# Sheet1.net
KiCad netlist of a schematic drawn in Altium Designer
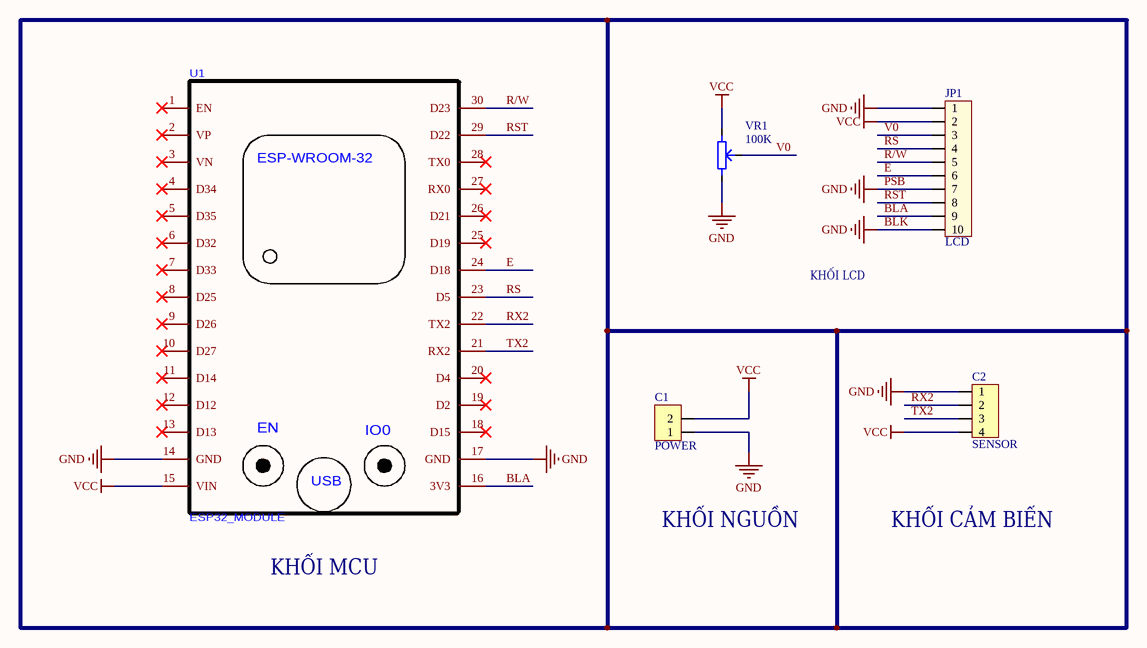
[diagram p0: Sheet1.SchDoc]

(export (version "E")
  (design (tool "Eeschema 10.0.6"))
  (components
    (comp (ref "C1")
      (value "POWER")
      (footprint "Header2")
      (description "Header IDC, 2 x 1 Pin Vertical 2.54mm Pitch (Non-Boxed, Male)")
      (fields
        (field (name "MANUFACTURER") "Würth Elektronik eiSos GmbH")
        (field (name "PARTNO") "613002143121")
        (field (name "CREATED BY") "Karrer Zheng")
      )
      (libsource (lib "myLib_v1") (part "Header2"))
    )
    (comp (ref "C2")
      (value "SENSOR")
      (footprint "Header4")
      (description "Header IDC, 4 x 1 Pin Vertical 2.54mm Pitch (Non-Boxed, Male)")
      (fields
        (field (name "MANUFACTURER") "Würth Elektronik eiSos GmbH")
        (field (name "PARTNO") "613002143121")
        (field (name "CREATED BY") "Karrer Zheng")
      )
      (libsource (lib "myLib_v1") (part "Header4"))
    )
    (comp (ref "JP1")
      (value "LCD")
      (footprint "Header10")
      (description "Connector 10")
      (libsource (lib "myLib_v1") (part "Header10"))
    )
    (comp (ref "U1")
      (value "ESP32_MODULE")
      (footprint "ESP32-WIFIMODULE-FOOTPRINT")
      (libsource (lib "myLib_v1") (part "ESP32_MODULE copy"))
    )
    (comp (ref "VR1")
      (value "100K")
      (footprint "Bien Tro Tam Giac Dung")
      (description "Cắm")
      (libsource (lib "Altium_Lib_by_KhueNguyenCreator") (part "Bien tro tam giac 100K Dung"))
    )
  )
  (nets
    (net (code "1") (name "/BLA") (class "Default")
      (node (ref "JP1") (pin "9") (pinfunction "9_9") (pintype "passive"))
      (node (ref "U1") (pin "16") (pinfunction "3V3_16") (pintype "passive"))
    )
    (net (code "2") (name "/E") (class "Default")
      (node (ref "JP1") (pin "6") (pinfunction "6_6") (pintype "passive"))
      (node (ref "U1") (pin "24") (pinfunction "D18_24") (pintype "passive"))
    )
    (net (code "3") (name "/RS") (class "Default")
      (node (ref "JP1") (pin "4") (pinfunction "4_4") (pintype "passive"))
      (node (ref "U1") (pin "23") (pinfunction "D5_23") (pintype "passive"))
    )
    (net (code "4") (name "/RST") (class "Default")
      (node (ref "JP1") (pin "8") (pinfunction "8_8") (pintype "passive"))
      (node (ref "U1") (pin "29") (pinfunction "D22_29") (pintype "passive"))
    )
    (net (code "5") (name "/RX2") (class "Default")
      (node (ref "C2") (pin "2") (pinfunction "2_2") (pintype "passive"))
      (node (ref "U1") (pin "22") (pinfunction "TX2_22") (pintype "passive"))
    )
    (net (code "6") (name "/R{slash}W") (class "Default")
      (node (ref "JP1") (pin "5") (pinfunction "5_5") (pintype "passive"))
      (node (ref "U1") (pin "30") (pinfunction "D23_30") (pintype "passive"))
    )
    (net (code "7") (name "/TX2") (class "Default")
      (node (ref "C2") (pin "3") (pinfunction "3_3") (pintype "passive"))
      (node (ref "U1") (pin "21") (pinfunction "RX2_21") (pintype "passive"))
    )
    (net (code "8") (name "/V0") (class "Default")
      (node (ref "JP1") (pin "3") (pinfunction "3_3") (pintype "passive"))
      (node (ref "VR1") (pin "2") (pinfunction "2_2") (pintype "passive"))
    )
    (net (code "9") (name "GND") (class "Default")
      (node (ref "C1") (pin "1") (pinfunction "1_1") (pintype "passive"))
      (node (ref "C2") (pin "1") (pinfunction "1_1") (pintype "passive"))
      (node (ref "JP1") (pin "1") (pinfunction "1_1") (pintype "passive"))
      (node (ref "JP1") (pin "10") (pinfunction "10_10") (pintype "passive"))
      (node (ref "JP1") (pin "7") (pinfunction "7_7") (pintype "passive"))
      (node (ref "U1") (pin "14") (pinfunction "GND_14") (pintype "passive"))
      (node (ref "U1") (pin "17") (pinfunction "GND_17") (pintype "passive"))
      (node (ref "VR1") (pin "3") (pinfunction "3_3") (pintype "passive"))
    )
    (net (code "10") (name "VCC") (class "Default")
      (node (ref "C1") (pin "2") (pinfunction "2_2") (pintype "passive"))
      (node (ref "C2") (pin "4") (pinfunction "4_4") (pintype "passive"))
      (node (ref "JP1") (pin "2") (pinfunction "2_2") (pintype "passive"))
      (node (ref "U1") (pin "15") (pinfunction "VIN_15") (pintype "passive"))
      (node (ref "VR1") (pin "1") (pinfunction "1_1") (pintype "passive"))
    )
    (net (code "11") (name "unconnected-(U1-D2-Pad19)") (class "Default")
      (node (ref "U1") (pin "19") (pinfunction "D2_19") (pintype "passive+no_connect"))
    )
    (net (code "12") (name "unconnected-(U1-D4-Pad20)") (class "Default")
      (node (ref "U1") (pin "20") (pinfunction "D4_20") (pintype "passive+no_connect"))
    )
    (net (code "13") (name "unconnected-(U1-D12-Pad12)") (class "Default")
      (node (ref "U1") (pin "12") (pinfunction "D12_12") (pintype "passive+no_connect"))
    )
    (net (code "14") (name "unconnected-(U1-D13-Pad13)") (class "Default")
      (node (ref "U1") (pin "13") (pinfunction "D13_13") (pintype "passive+no_connect"))
    )
    (net (code "15") (name "unconnected-(U1-D14-Pad11)") (class "Default")
      (node (ref "U1") (pin "11") (pinfunction "D14_11") (pintype "passive+no_connect"))
    )
    (net (code "16") (name "unconnected-(U1-D15-Pad18)") (class "Default")
      (node (ref "U1") (pin "18") (pinfunction "D15_18") (pintype "passive+no_connect"))
    )
    (net (code "17") (name "unconnected-(U1-D19-Pad25)") (class "Default")
      (node (ref "U1") (pin "25") (pinfunction "D19_25") (pintype "passive+no_connect"))
    )
    (net (code "18") (name "unconnected-(U1-D21-Pad26)") (class "Default")
      (node (ref "U1") (pin "26") (pinfunction "D21_26") (pintype "passive+no_connect"))
    )
    (net (code "19") (name "unconnected-(U1-D25-Pad8)") (class "Default")
      (node (ref "U1") (pin "8") (pinfunction "D25_8") (pintype "passive+no_connect"))
    )
    (net (code "20") (name "unconnected-(U1-D26-Pad9)") (class "Default")
      (node (ref "U1") (pin "9") (pinfunction "D26_9") (pintype "passive+no_connect"))
    )
    (net (code "21") (name "unconnected-(U1-D27-Pad10)") (class "Default")
      (node (ref "U1") (pin "10") (pinfunction "D27_10") (pintype "passive+no_connect"))
    )
    (net (code "22") (name "unconnected-(U1-D32-Pad6)") (class "Default")
      (node (ref "U1") (pin "6") (pinfunction "D32_6") (pintype "passive+no_connect"))
    )
    (net (code "23") (name "unconnected-(U1-D33-Pad7)") (class "Default")
      (node (ref "U1") (pin "7") (pinfunction "D33_7") (pintype "passive+no_connect"))
    )
    (net (code "24") (name "unconnected-(U1-D34-Pad4)") (class "Default")
      (node (ref "U1") (pin "4") (pinfunction "D34_4") (pintype "passive+no_connect"))
    )
    (net (code "25") (name "unconnected-(U1-D35-Pad5)") (class "Default")
      (node (ref "U1") (pin "5") (pinfunction "D35_5") (pintype "passive+no_connect"))
    )
    (net (code "26") (name "unconnected-(U1-EN-Pad1)") (class "Default")
      (node (ref "U1") (pin "1") (pinfunction "EN_1") (pintype "passive+no_connect"))
    )
    (net (code "27") (name "unconnected-(U1-RX0-Pad27)") (class "Default")
      (node (ref "U1") (pin "27") (pinfunction "RX0_27") (pintype "passive+no_connect"))
    )
    (net (code "28") (name "unconnected-(U1-TX0-Pad28)") (class "Default")
      (node (ref "U1") (pin "28") (pinfunction "TX0_28") (pintype "passive+no_connect"))
    )
    (net (code "29") (name "unconnected-(U1-VN-Pad3)") (class "Default")
      (node (ref "U1") (pin "3") (pinfunction "VN_3") (pintype "passive+no_connect"))
    )
    (net (code "30") (name "unconnected-(U1-VP-Pad2)") (class "Default")
      (node (ref "U1") (pin "2") (pinfunction "VP_2") (pintype "passive+no_connect"))
    )
  )
)
